# shield.net
KiCad netlist of a schematic drawn in EAGLE
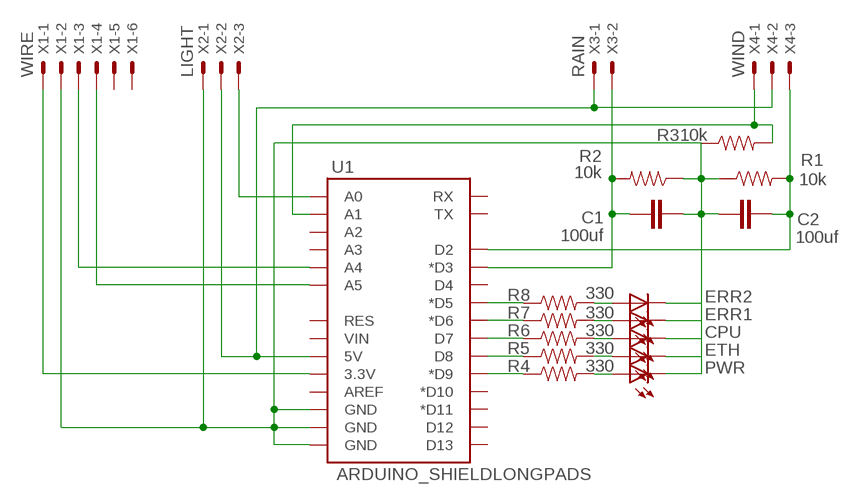
[diagram p0: schematic, sheet 1]

(export (version "E")
  (design (tool "Eeschema 10.0.6"))
  (components
    (comp (ref "C1")
      (value "100uf")
      (footprint "eagle-import:CAP-PTH-SMALL-KIT")
      (libsource (lib "eagle-import") (part "CAPKIT"))
    )
    (comp (ref "C2")
      (value "100uf")
      (footprint "eagle-import:CAP-PTH-SMALL-KIT")
      (libsource (lib "eagle-import") (part "CAPKIT"))
    )
    (comp (ref "CPU")
      (value "LED3MM")
      (footprint "eagle-import:LED3MM")
      (libsource (lib "eagle-import") (part "LED3MM"))
    )
    (comp (ref "ERR1")
      (value "LED3MM")
      (footprint "eagle-import:LED3MM")
      (libsource (lib "eagle-import") (part "LED3MM"))
    )
    (comp (ref "ERR2")
      (value "LED3MM")
      (footprint "eagle-import:LED3MM")
      (libsource (lib "eagle-import") (part "LED3MM"))
    )
    (comp (ref "ETH")
      (value "LED3MM")
      (footprint "eagle-import:LED3MM")
      (libsource (lib "eagle-import") (part "LED3MM"))
    )
    (comp (ref "PWR")
      (value "LED3MM")
      (footprint "eagle-import:LED3MM")
      (libsource (lib "eagle-import") (part "LED3MM"))
    )
    (comp (ref "R1")
      (value "10k")
      (footprint "eagle-import:AXIAL-0.3-KIT")
      (libsource (lib "eagle-import") (part "RESISTORKIT"))
    )
    (comp (ref "R2")
      (value "10k")
      (footprint "eagle-import:AXIAL-0.3-KIT")
      (libsource (lib "eagle-import") (part "RESISTORKIT"))
    )
    (comp (ref "R3")
      (value "10k")
      (footprint "eagle-import:AXIAL-0.3-KIT")
      (libsource (lib "eagle-import") (part "RESISTORKIT"))
    )
    (comp (ref "R4")
      (value "330")
      (footprint "eagle-import:AXIAL-0.3-KIT")
      (libsource (lib "eagle-import") (part "RESISTORKIT"))
    )
    (comp (ref "R5")
      (value "330")
      (footprint "eagle-import:AXIAL-0.3-KIT")
      (libsource (lib "eagle-import") (part "RESISTORKIT"))
    )
    (comp (ref "R6")
      (value "330")
      (footprint "eagle-import:AXIAL-0.3-KIT")
      (libsource (lib "eagle-import") (part "RESISTORKIT"))
    )
    (comp (ref "R7")
      (value "330")
      (footprint "eagle-import:AXIAL-0.3-KIT")
      (libsource (lib "eagle-import") (part "RESISTORKIT"))
    )
    (comp (ref "R8")
      (value "330")
      (footprint "eagle-import:AXIAL-0.3-KIT")
      (libsource (lib "eagle-import") (part "RESISTORKIT"))
    )
    (comp (ref "U1")
      (value "ARDUINO_SHIELDLONGPADS")
      (footprint "eagle-import:DUEMILANOVE_SHIELD_LONGPADS")
      (libsource (lib "eagle-import") (part "ARDUINO_SHIELDLONGPADS"))
    )
    (comp (ref "X1")
      (value "WIRE")
      (footprint "eagle-import:22-23-2061")
      (fields (field (name "MF") "MOLEX") (field (name "MPN") "22-23-2061"))
      (libsource (lib "eagle-import") (part "22-23-2061"))
    )
    (comp (ref "X2")
      (value "LIGHT")
      (footprint "eagle-import:22-23-2031")
      (fields (field (name "MF") "MOLEX") (field (name "MPN") "22-23-2031"))
      (libsource (lib "eagle-import") (part "22-23-2031"))
    )
    (comp (ref "X3")
      (value "RAIN")
      (footprint "eagle-import:22-23-2021")
      (fields (field (name "MF") "MOLEX") (field (name "MPN") "22-23-2021"))
      (libsource (lib "eagle-import") (part "22-23-2021"))
    )
    (comp (ref "X4")
      (value "WIND")
      (footprint "eagle-import:22-23-2031")
      (fields (field (name "MF") "MOLEX") (field (name "MPN") "22-23-2031"))
      (libsource (lib "eagle-import") (part "22-23-2031"))
    )
  )
  (nets
    (net (code "1") (name "Net-(CPU-C)") (class "Default")
      (node (ref "C1") (pin "2") (pinfunction "2_2") (pintype "passive"))
      (node (ref "C2") (pin "1") (pinfunction "1_1") (pintype "passive"))
      (node (ref "CPU") (pin "K") (pinfunction "C_K") (pintype "passive"))
      (node (ref "ERR1") (pin "K") (pinfunction "C_K") (pintype "passive"))
      (node (ref "ERR2") (pin "K") (pinfunction "C_K") (pintype "passive"))
      (node (ref "ETH") (pin "K") (pinfunction "C_K") (pintype "passive"))
      (node (ref "PWR") (pin "K") (pinfunction "C_K") (pintype "passive"))
      (node (ref "R1") (pin "P$1") (pinfunction "1_P$1") (pintype "passive"))
      (node (ref "R2") (pin "P$1") (pinfunction "1_P$1") (pintype "passive"))
      (node (ref "R3") (pin "P$1") (pinfunction "1_P$1") (pintype "passive"))
      (node (ref "U1") (pin "GND@0") (pinfunction "GND_GND@0") (pintype "bidirectional"))
      (node (ref "U1") (pin "GND@1") (pinfunction "GND_GND@1") (pintype "bidirectional"))
      (node (ref "U1") (pin "GND@2") (pinfunction "GND_GND@2") (pintype "bidirectional"))
      (node (ref "X1") (pin "2") (pinfunction "S_2") (pintype "passive"))
      (node (ref "X2") (pin "1") (pinfunction "S_1") (pintype "passive"))
    )
    (net (code "2") (name "Net-(R1-2)") (class "Default")
      (node (ref "C2") (pin "2") (pinfunction "2_2") (pintype "passive"))
      (node (ref "R1") (pin "P$2") (pinfunction "2_P$2") (pintype "passive"))
      (node (ref "U1") (pin "D2") (pinfunction "D2_D2") (pintype "bidirectional"))
      (node (ref "X4") (pin "3") (pinfunction "S_3") (pintype "passive"))
    )
    (net (code "3") (name "Net-(R2-2)") (class "Default")
      (node (ref "C1") (pin "1") (pinfunction "1_1") (pintype "passive"))
      (node (ref "R2") (pin "P$2") (pinfunction "2_P$2") (pintype "passive"))
      (node (ref "U1") (pin "D3") (pinfunction "*D3_D3") (pintype "bidirectional"))
      (node (ref "X3") (pin "2") (pinfunction "S_2") (pintype "passive"))
    )
    (net (code "4") (name "Net-(R3-2)") (class "Default")
      (node (ref "R3") (pin "P$2") (pinfunction "2_P$2") (pintype "passive"))
      (node (ref "U1") (pin "A1") (pinfunction "A1_A1") (pintype "bidirectional"))
      (node (ref "X4") (pin "1") (pinfunction "S_1") (pintype "passive"))
    )
    (net (code "5") (name "Net-(R4-1)") (class "Default")
      (node (ref "R4") (pin "P$1") (pinfunction "1_P$1") (pintype "passive"))
      (node (ref "U1") (pin "D9") (pinfunction "*D9_D9") (pintype "bidirectional"))
    )
    (net (code "6") (name "Net-(R4-2)") (class "Default")
      (node (ref "PWR") (pin "A") (pinfunction "A_A") (pintype "passive"))
      (node (ref "R4") (pin "P$2") (pinfunction "2_P$2") (pintype "passive"))
    )
    (net (code "7") (name "Net-(R5-1)") (class "Default")
      (node (ref "R5") (pin "P$1") (pinfunction "1_P$1") (pintype "passive"))
      (node (ref "U1") (pin "D8") (pinfunction "D8_D8") (pintype "bidirectional"))
    )
    (net (code "8") (name "Net-(R5-2)") (class "Default")
      (node (ref "ETH") (pin "A") (pinfunction "A_A") (pintype "passive"))
      (node (ref "R5") (pin "P$2") (pinfunction "2_P$2") (pintype "passive"))
    )
    (net (code "9") (name "Net-(R6-1)") (class "Default")
      (node (ref "R6") (pin "P$1") (pinfunction "1_P$1") (pintype "passive"))
      (node (ref "U1") (pin "D7") (pinfunction "D7_D7") (pintype "bidirectional"))
    )
    (net (code "10") (name "Net-(R6-2)") (class "Default")
      (node (ref "CPU") (pin "A") (pinfunction "A_A") (pintype "passive"))
      (node (ref "R6") (pin "P$2") (pinfunction "2_P$2") (pintype "passive"))
    )
    (net (code "11") (name "Net-(R7-1)") (class "Default")
      (node (ref "R7") (pin "P$1") (pinfunction "1_P$1") (pintype "passive"))
      (node (ref "U1") (pin "D6") (pinfunction "*D6_D6") (pintype "bidirectional"))
    )
    (net (code "12") (name "Net-(R7-2)") (class "Default")
      (node (ref "ERR1") (pin "A") (pinfunction "A_A") (pintype "passive"))
      (node (ref "R7") (pin "P$2") (pinfunction "2_P$2") (pintype "passive"))
    )
    (net (code "13") (name "Net-(R8-1)") (class "Default")
      (node (ref "R8") (pin "P$1") (pinfunction "1_P$1") (pintype "passive"))
      (node (ref "U1") (pin "D5") (pinfunction "*D5_D5") (pintype "bidirectional"))
    )
    (net (code "14") (name "Net-(R8-2)") (class "Default")
      (node (ref "ERR2") (pin "A") (pinfunction "A_A") (pintype "passive"))
      (node (ref "R8") (pin "P$2") (pinfunction "2_P$2") (pintype "passive"))
    )
    (net (code "15") (name "Net-(X1A-S)") (class "Default")
      (node (ref "U1") (pin "3.3V") (pinfunction "3.3V_3.3V") (pintype "bidirectional"))
      (node (ref "X1") (pin "1") (pinfunction "S_1") (pintype "passive"))
    )
    (net (code "16") (name "Net-(X1C-S)") (class "Default")
      (node (ref "U1") (pin "A4") (pinfunction "A4_A4") (pintype "bidirectional"))
      (node (ref "X1") (pin "3") (pinfunction "S_3") (pintype "passive"))
    )
    (net (code "17") (name "Net-(X1D-S)") (class "Default")
      (node (ref "U1") (pin "A5") (pinfunction "A5_A5") (pintype "bidirectional"))
      (node (ref "X1") (pin "4") (pinfunction "S_4") (pintype "passive"))
    )
    (net (code "18") (name "Net-(X2B-S)") (class "Default")
      (node (ref "U1") (pin "5V") (pinfunction "5V_5V") (pintype "bidirectional"))
      (node (ref "X2") (pin "2") (pinfunction "S_2") (pintype "passive"))
      (node (ref "X3") (pin "1") (pinfunction "S_1") (pintype "passive"))
      (node (ref "X4") (pin "2") (pinfunction "S_2") (pintype "passive"))
    )
    (net (code "19") (name "Net-(X2C-S)") (class "Default")
      (node (ref "U1") (pin "A0") (pinfunction "A0_A0") (pintype "bidirectional"))
      (node (ref "X2") (pin "3") (pinfunction "S_3") (pintype "passive"))
    )
    (net (code "20") (name "unconnected-(U1-*D10-PadD10)") (class "Default")
      (node (ref "U1") (pin "D10") (pinfunction "*D10_D10") (pintype "bidirectional"))
    )
    (net (code "21") (name "unconnected-(U1-*D11-PadD11)") (class "Default")
      (node (ref "U1") (pin "D11") (pinfunction "*D11_D11") (pintype "bidirectional"))
    )
    (net (code "22") (name "unconnected-(U1-PadA2)") (class "Default")
      (node (ref "U1") (pin "A2") (pinfunction "A2_A2") (pintype "bidirectional"))
    )
    (net (code "23") (name "unconnected-(U1-PadA3)") (class "Default")
      (node (ref "U1") (pin "A3") (pinfunction "A3_A3") (pintype "bidirectional"))
    )
    (net (code "24") (name "unconnected-(U1-PadAREF)") (class "Default")
      (node (ref "U1") (pin "AREF") (pinfunction "AREF_AREF") (pintype "bidirectional"))
    )
    (net (code "25") (name "unconnected-(U1-PadD4)") (class "Default")
      (node (ref "U1") (pin "D4") (pinfunction "D4_D4") (pintype "bidirectional"))
    )
    (net (code "26") (name "unconnected-(U1-PadD12)") (class "Default")
      (node (ref "U1") (pin "D12") (pinfunction "D12_D12") (pintype "bidirectional"))
    )
    (net (code "27") (name "unconnected-(U1-PadD13)") (class "Default")
      (node (ref "U1") (pin "D13") (pinfunction "D13_D13") (pintype "bidirectional"))
    )
    (net (code "28") (name "unconnected-(U1-PadRES)") (class "Default")
      (node (ref "U1") (pin "RES") (pinfunction "RES_RES") (pintype "bidirectional"))
    )
    (net (code "29") (name "unconnected-(U1-PadRX)") (class "Default")
      (node (ref "U1") (pin "RX") (pinfunction "RX_RX") (pintype "bidirectional"))
    )
    (net (code "30") (name "unconnected-(U1-PadTX)") (class "Default")
      (node (ref "U1") (pin "TX") (pinfunction "TX_TX") (pintype "bidirectional"))
    )
    (net (code "31") (name "unconnected-(U1-PadVIN)") (class "Default")
      (node (ref "U1") (pin "VIN") (pinfunction "VIN_VIN") (pintype "bidirectional"))
    )
    (net (code "32") (name "unconnected-(X1E-S-Pad5)") (class "Default")
      (node (ref "X1") (pin "5") (pinfunction "S_5") (pintype "passive"))
    )
    (net (code "33") (name "unconnected-(X1F-S-Pad6)") (class "Default")
      (node (ref "X1") (pin "6") (pinfunction "S_6") (pintype "passive"))
    )
  )
)
